# Screen_Board.net
KiCad netlist of a schematic drawn in EAGLE
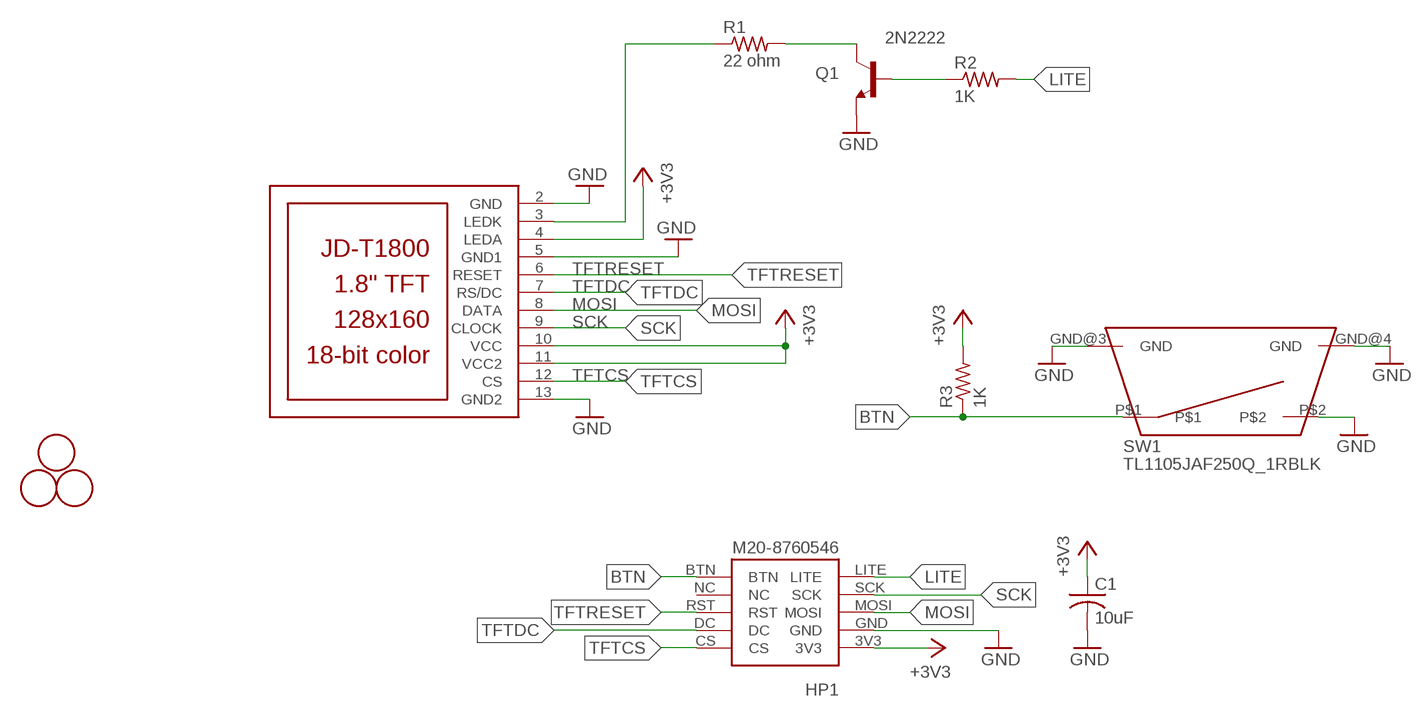
[diagram p0: schematic, sheet 1]

(export (version "E")
  (design (tool "Eeschema 10.0.6"))
  (components
    (comp (ref "C1")
      (value "10uF")
      (footprint "eagle-import:C0805K")
      (libsource (lib "eagle-import") (part "C-USC0805K"))
    )
    (comp (ref "HP1")
      (value "M20-8760546")
      (footprint "eagle-import:M20-8760546")
      (libsource (lib "eagle-import") (part "M20-8760546"))
    )
    (comp (ref "Q1")
      (value "2N2222")
      (footprint "eagle-import:SOT23-BEC")
      (libsource (lib "eagle-import") (part "-NPN-SOT23-BECMMBT2222ALT1"))
    )
    (comp (ref "R1")
      (value "22 ohm")
      (footprint "eagle-import:R0805")
      (libsource (lib "eagle-import") (part "R-US_R0805"))
    )
    (comp (ref "R2")
      (value "1K")
      (footprint "eagle-import:R0805")
      (libsource (lib "eagle-import") (part "R-US_R0805"))
    )
    (comp (ref "R3")
      (value "1K")
      (footprint "eagle-import:R0805")
      (libsource (lib "eagle-import") (part "R-US_R0805"))
    )
    (comp (ref "SW1")
      (value "TL1105JAF250Q_1RBLK")
      (footprint "eagle-import:TL1105JAF250Q_1RBLK")
      (libsource (lib "eagle-import") (part "TL1105JAF250Q_1RBLK"))
    )
    (comp (ref "U$1")
      (value "JD-T1800")
      (footprint "eagle-import:JD-T1800")
      (libsource (lib "eagle-import") (part "JD-T1800"))
    )
    (comp (ref "U$3")
      (value "FIDUCIAL")
      (footprint "eagle-import:FIDUCIAL_1MM")
      (libsource (lib "eagle-import") (part "FIDUCIAL"))
    )
    (comp (ref "U$4")
      (value "FIDUCIAL")
      (footprint "eagle-import:FIDUCIAL_1MM")
      (libsource (lib "eagle-import") (part "FIDUCIAL"))
    )
    (comp (ref "U$5")
      (value "FIDUCIAL")
      (footprint "eagle-import:FIDUCIAL_1MM")
      (libsource (lib "eagle-import") (part "FIDUCIAL"))
    )
  )
  (nets
    (net (code "1") (name "+3V3") (class "Default")
      (node (ref "C1") (pin "1") (pinfunction "1_1") (pintype "passive"))
      (node (ref "HP1") (pin "3V3") (pinfunction "3V3_3V3") (pintype "bidirectional"))
      (node (ref "R3") (pin "2") (pinfunction "2_2") (pintype "passive"))
      (node (ref "U$1") (pin "10") (pinfunction "VCC_10") (pintype "power_in"))
      (node (ref "U$1") (pin "11") (pinfunction "VCC2_11") (pintype "power_in"))
      (node (ref "U$1") (pin "4") (pinfunction "LEDA_4") (pintype "input"))
    )
    (net (code "2") (name "BTN") (class "Default")
      (node (ref "HP1") (pin "BTN") (pinfunction "BTN_BTN") (pintype "bidirectional"))
      (node (ref "R3") (pin "1") (pinfunction "1_1") (pintype "passive"))
      (node (ref "SW1") (pin "P$1") (pinfunction "P$1_P$1") (pintype "bidirectional"))
    )
    (net (code "3") (name "GND") (class "Default")
      (node (ref "C1") (pin "2") (pinfunction "2_2") (pintype "passive"))
      (node (ref "HP1") (pin "GND") (pinfunction "GND_GND") (pintype "bidirectional"))
      (node (ref "Q1") (pin "E") (pinfunction "E_E") (pintype "passive"))
      (node (ref "SW1") (pin "GND@3") (pinfunction "GND_GND@3") (pintype "bidirectional"))
      (node (ref "SW1") (pin "GND@4") (pinfunction "GND_GND@4") (pintype "bidirectional"))
      (node (ref "SW1") (pin "P$2") (pinfunction "P$2_P$2") (pintype "bidirectional"))
      (node (ref "U$1") (pin "13") (pinfunction "GND2_13") (pintype "power_in"))
      (node (ref "U$1") (pin "2") (pinfunction "GND_2") (pintype "power_in"))
      (node (ref "U$1") (pin "5") (pinfunction "GND1_5") (pintype "power_in"))
    )
    (net (code "4") (name "LITE") (class "Default")
      (node (ref "HP1") (pin "LITE") (pinfunction "LITE_LITE") (pintype "bidirectional"))
      (node (ref "R2") (pin "2") (pinfunction "2_2") (pintype "passive"))
    )
    (net (code "5") (name "MOSI") (class "Default")
      (node (ref "HP1") (pin "MOSI") (pinfunction "MOSI_MOSI") (pintype "bidirectional"))
      (node (ref "U$1") (pin "8") (pinfunction "DATA_8") (pintype "bidirectional"))
    )
    (net (code "6") (name "Net-(Q1-PadB)") (class "Default")
      (node (ref "Q1") (pin "B") (pinfunction "B_B") (pintype "passive"))
      (node (ref "R2") (pin "1") (pinfunction "1_1") (pintype "passive"))
    )
    (net (code "7") (name "Net-(Q1-PadC)") (class "Default")
      (node (ref "Q1") (pin "C") (pinfunction "C_C") (pintype "passive"))
      (node (ref "R1") (pin "2") (pinfunction "2_2") (pintype "passive"))
    )
    (net (code "8") (name "Net-(U$1-LEDK)") (class "Default")
      (node (ref "R1") (pin "1") (pinfunction "1_1") (pintype "passive"))
      (node (ref "U$1") (pin "3") (pinfunction "LEDK_3") (pintype "input"))
    )
    (net (code "9") (name "SCK") (class "Default")
      (node (ref "HP1") (pin "SCK") (pinfunction "SCK_SCK") (pintype "bidirectional"))
      (node (ref "U$1") (pin "9") (pinfunction "CLOCK_9") (pintype "input"))
    )
    (net (code "10") (name "TFTCS") (class "Default")
      (node (ref "HP1") (pin "CS") (pinfunction "CS_CS") (pintype "bidirectional"))
      (node (ref "U$1") (pin "12") (pinfunction "CS_12") (pintype "input"))
    )
    (net (code "11") (name "TFTDC") (class "Default")
      (node (ref "HP1") (pin "DC") (pinfunction "DC_DC") (pintype "bidirectional"))
      (node (ref "U$1") (pin "7") (pinfunction "RS/DC_7") (pintype "input"))
    )
    (net (code "12") (name "TFTRESET") (class "Default")
      (node (ref "HP1") (pin "RST") (pinfunction "RST_RST") (pintype "bidirectional"))
      (node (ref "U$1") (pin "6") (pinfunction "RESET_6") (pintype "input"))
    )
    (net (code "13") (name "unconnected-(HP1-PadNC)") (class "Default")
      (node (ref "HP1") (pin "NC") (pinfunction "NC_NC") (pintype "bidirectional"))
    )
  )
)
